# 301_FrameUSB.net
KiCad netlist of a schematic drawn in Altium Designer
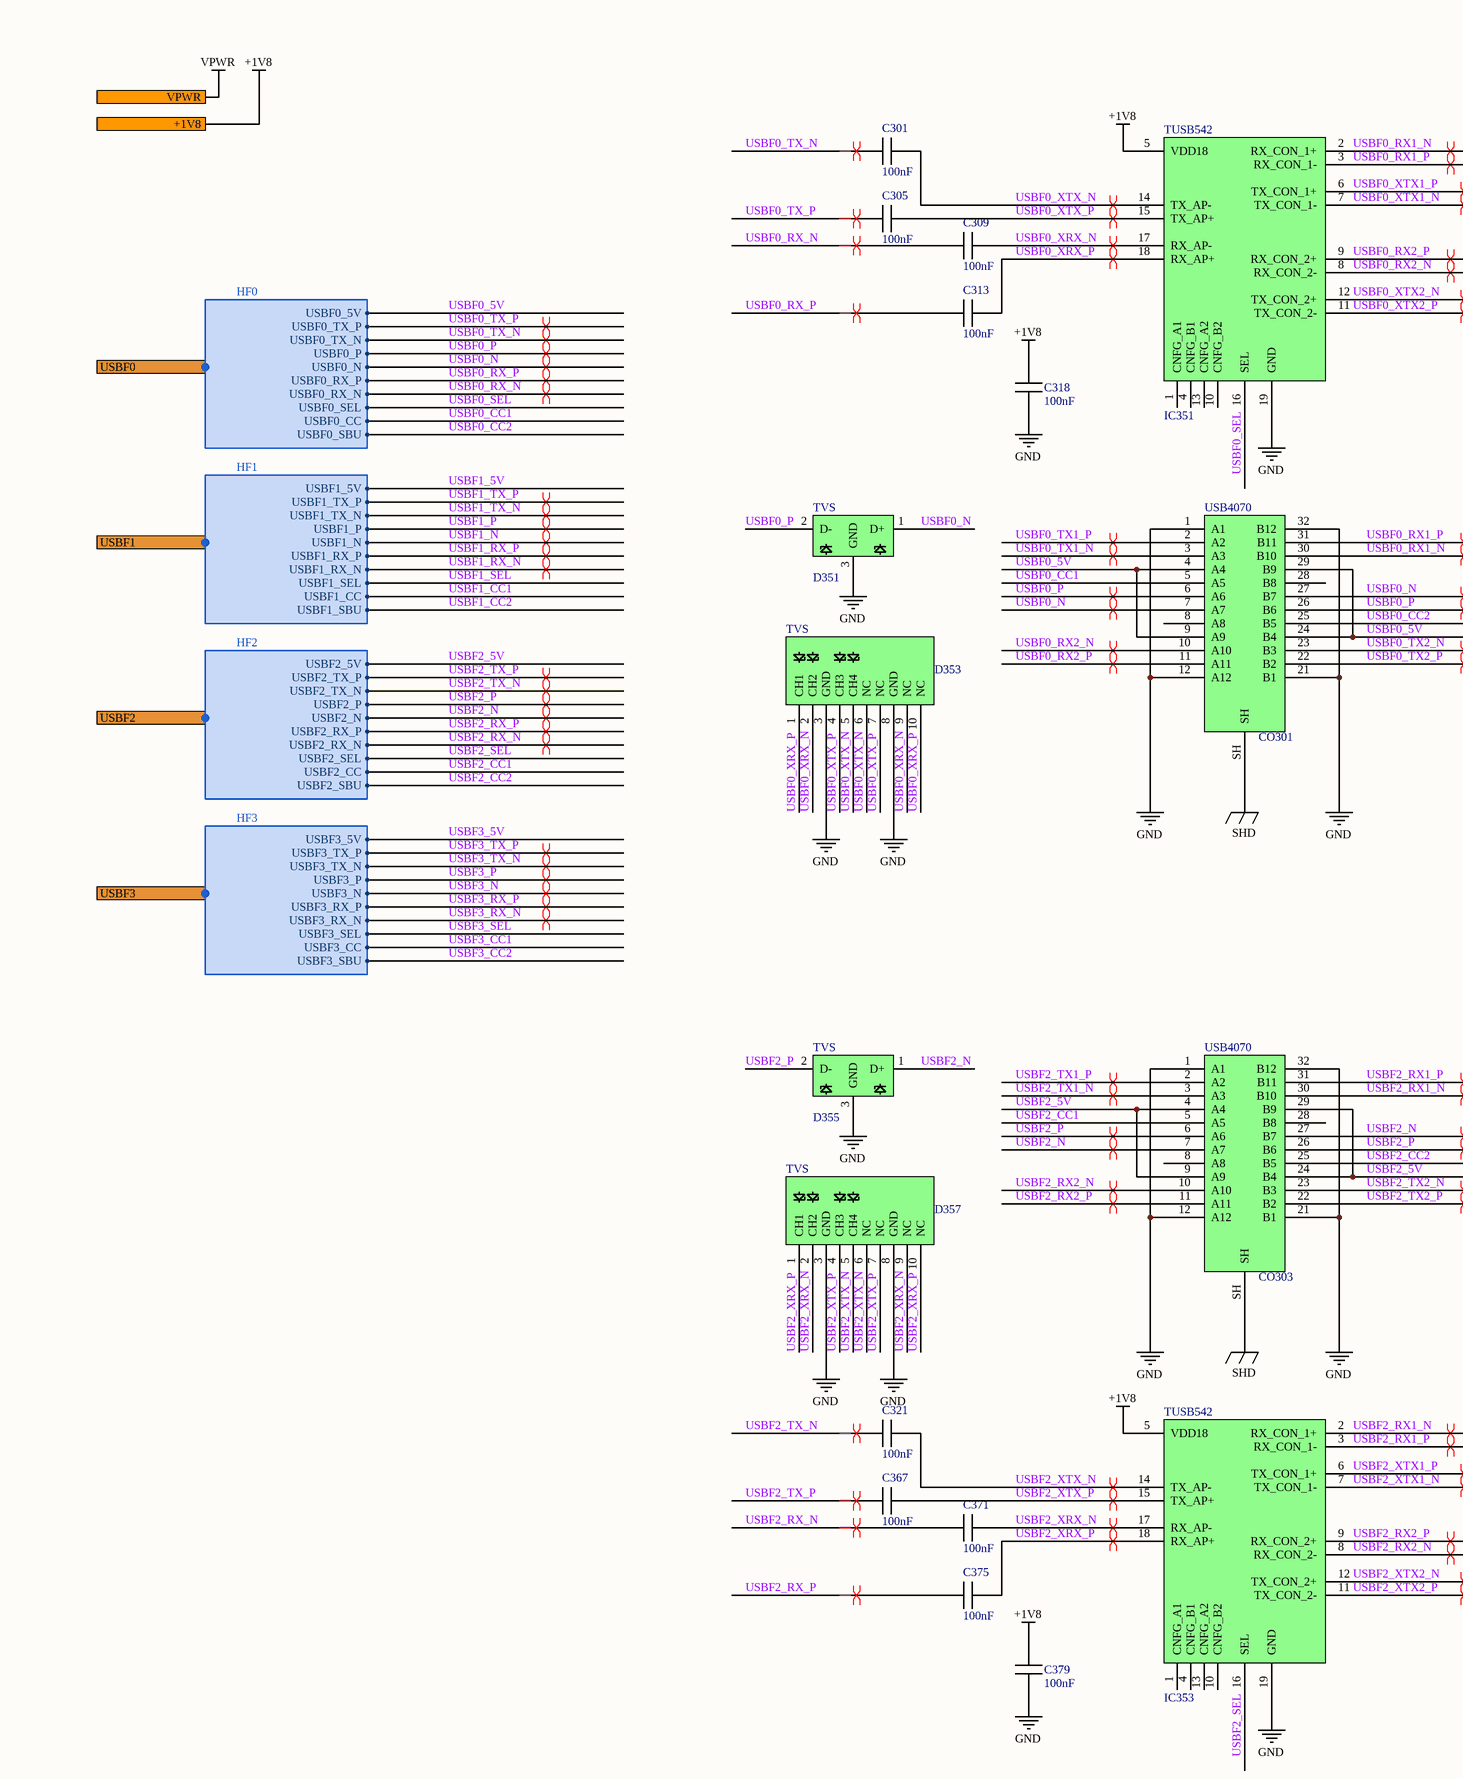
[diagram p0: 301_FrameUSB.SchDoc, top left]
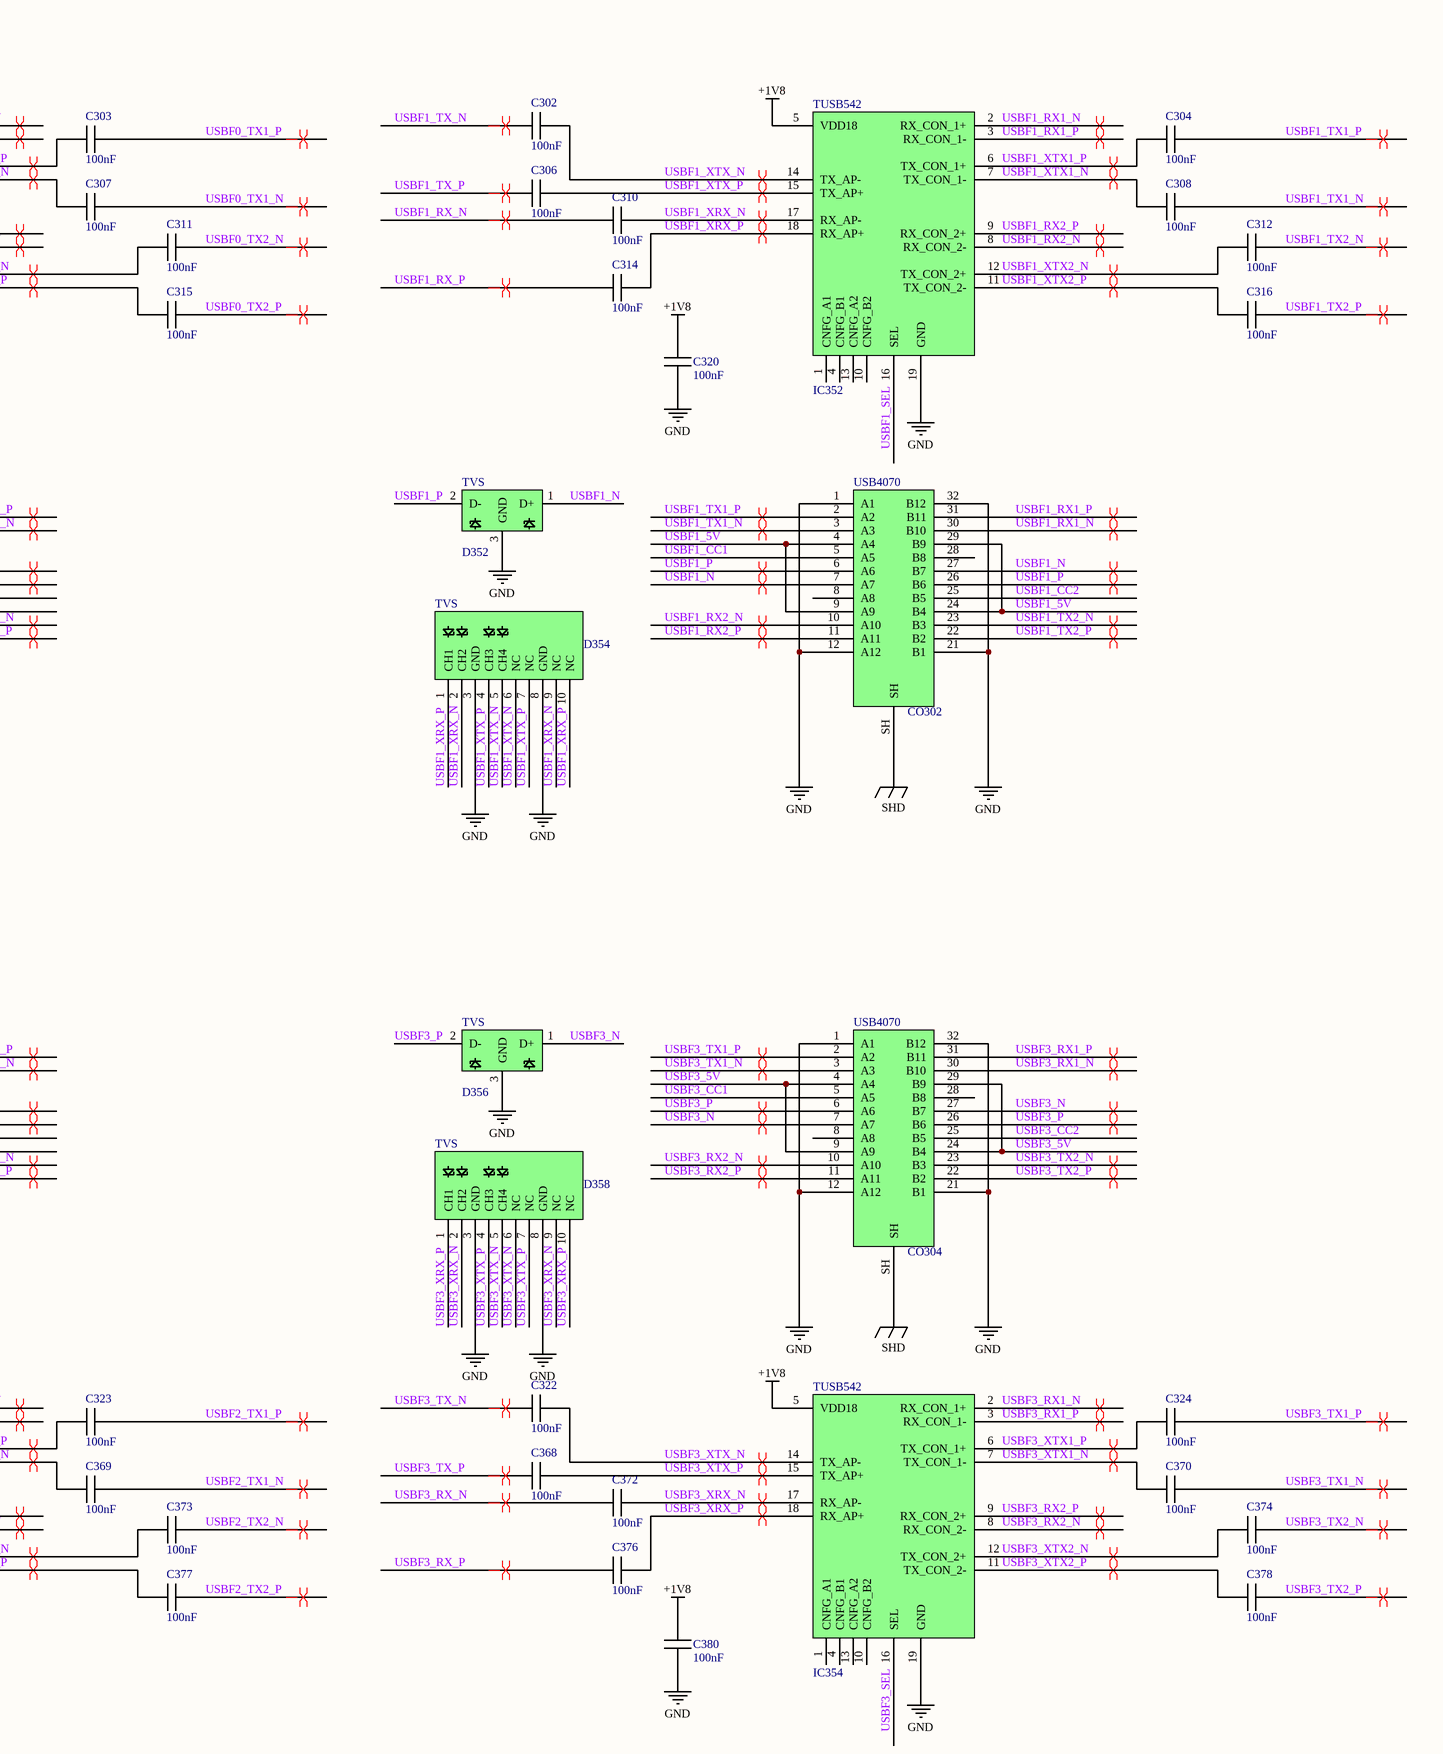
[diagram p1: 301_FrameUSB.SchDoc, top right]
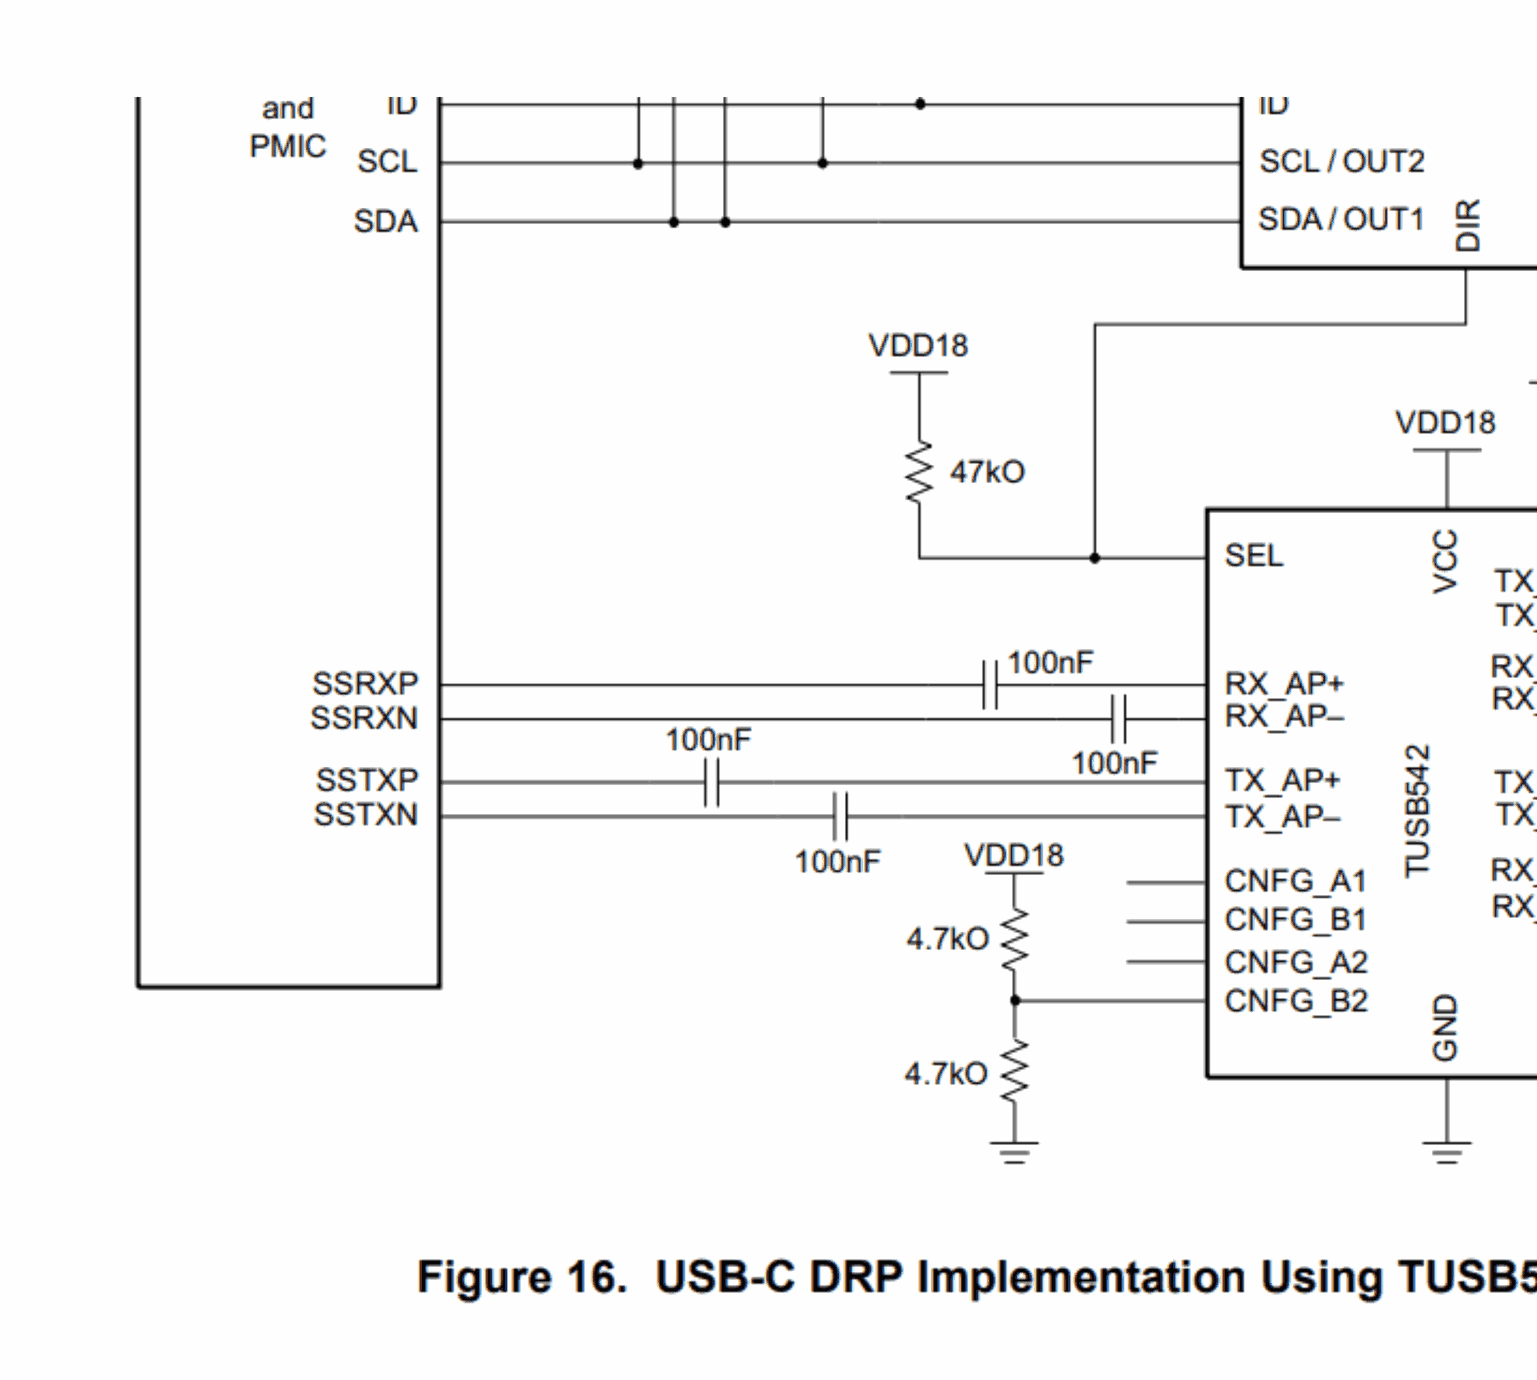
[diagram p2: 301_FrameUSB.SchDoc, bottom left]
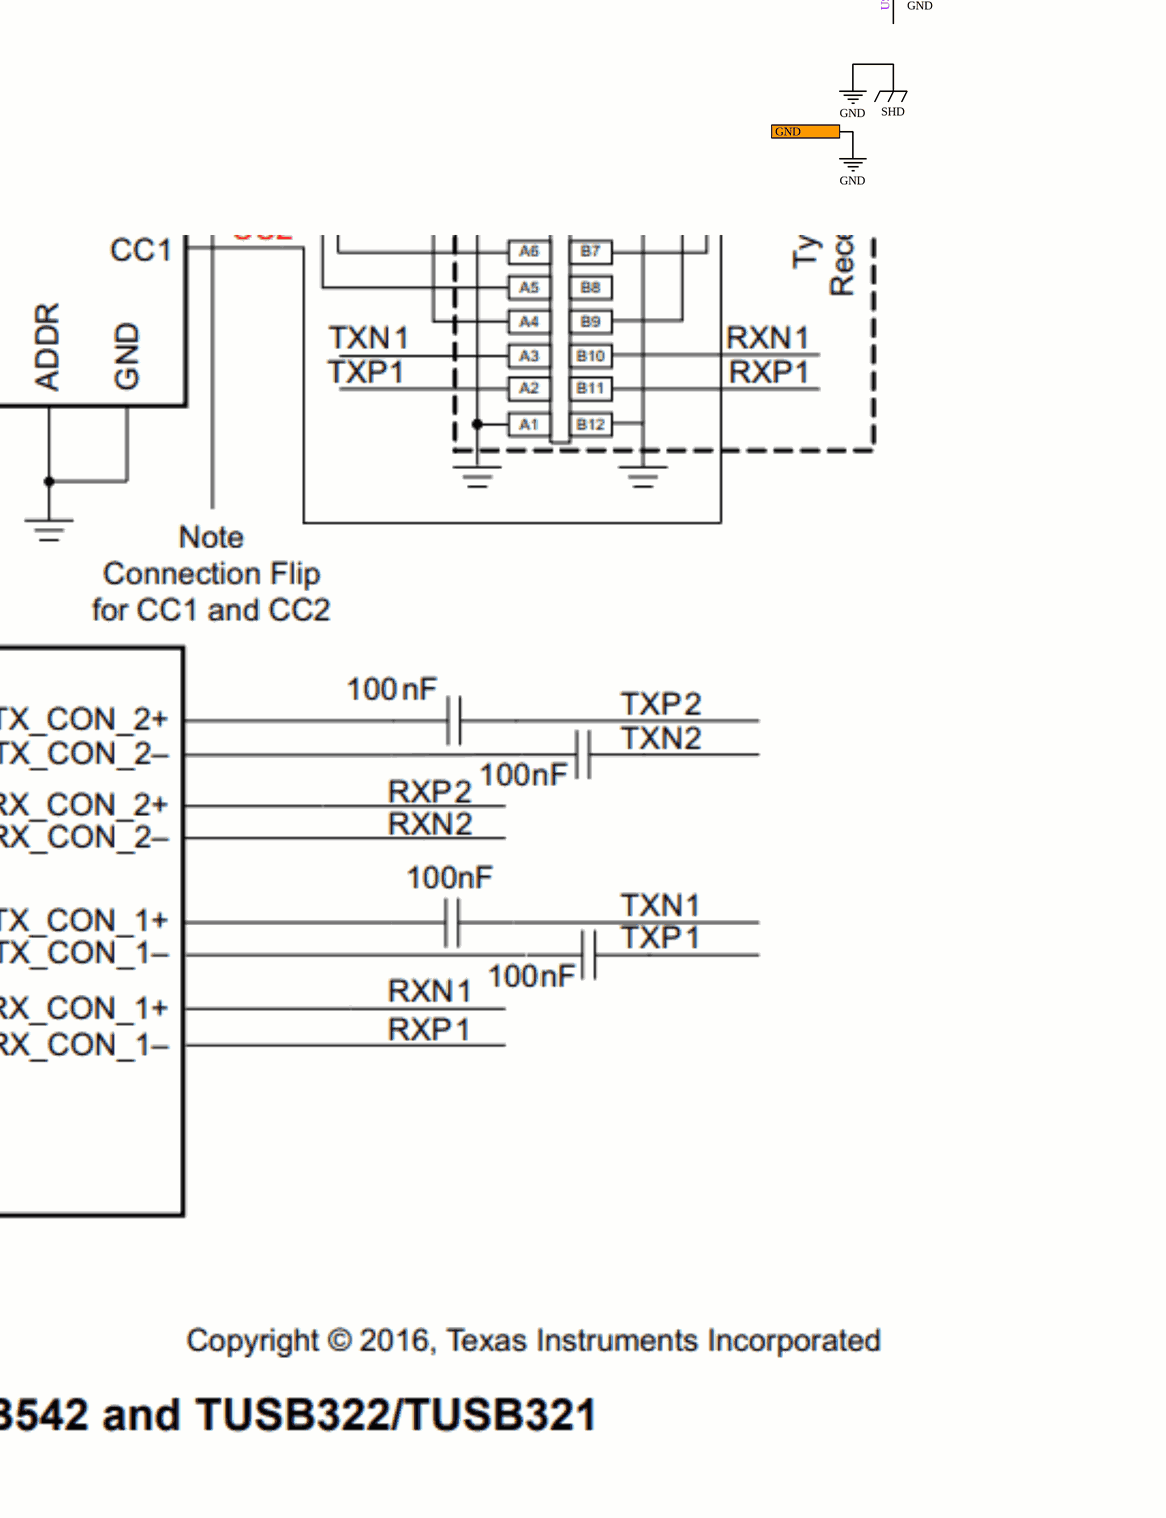
[diagram p3: 301_FrameUSB.SchDoc, bottom right]

(export (version "E")
  (design (tool "Eeschema 10.0.6"))
  (components
    (comp (ref "C301")
      (value "100nF")
      (footprint "C0402")
      (description "100nF 16V 10% X7R")
      (fields
        (field (name "REFVAL") "100nF")
        (field (name "PART NUMBER") "CA0010")
        (field (name "MANFACTPART") "GCM155R71C104KA55D")
      )
      (libsource (lib "GTS_Database") (part "C"))
    )
    (comp (ref "C302")
      (value "100nF")
      (footprint "C0402")
      (description "100nF 16V 10% X7R")
      (fields
        (field (name "REFVAL") "100nF")
        (field (name "PART NUMBER") "CA0010")
        (field (name "MANFACTPART") "GCM155R71C104KA55D")
      )
      (libsource (lib "GTS_Database") (part "C"))
    )
    (comp (ref "C303")
      (value "100nF")
      (footprint "C0402")
      (description "100nF 16V 10% X7R")
      (fields
        (field (name "REFVAL") "100nF")
        (field (name "PART NUMBER") "CA0010")
        (field (name "MANFACTPART") "GCM155R71C104KA55D")
      )
      (libsource (lib "GTS_Database") (part "C"))
    )
    (comp (ref "C304")
      (value "100nF")
      (footprint "C0402")
      (description "100nF 16V 10% X7R")
      (fields
        (field (name "REFVAL") "100nF")
        (field (name "PART NUMBER") "CA0010")
        (field (name "MANFACTPART") "GCM155R71C104KA55D")
      )
      (libsource (lib "GTS_Database") (part "C"))
    )
    (comp (ref "C305")
      (value "100nF")
      (footprint "C0402")
      (description "100nF 16V 10% X7R")
      (fields
        (field (name "REFVAL") "100nF")
        (field (name "PART NUMBER") "CA0010")
        (field (name "MANFACTPART") "GCM155R71C104KA55D")
      )
      (libsource (lib "GTS_Database") (part "C"))
    )
    (comp (ref "C306")
      (value "100nF")
      (footprint "C0402")
      (description "100nF 16V 10% X7R")
      (fields
        (field (name "REFVAL") "100nF")
        (field (name "PART NUMBER") "CA0010")
        (field (name "MANFACTPART") "GCM155R71C104KA55D")
      )
      (libsource (lib "GTS_Database") (part "C"))
    )
    (comp (ref "C307")
      (value "100nF")
      (footprint "C0402")
      (description "100nF 16V 10% X7R")
      (fields
        (field (name "REFVAL") "100nF")
        (field (name "PART NUMBER") "CA0010")
        (field (name "MANFACTPART") "GCM155R71C104KA55D")
      )
      (libsource (lib "GTS_Database") (part "C"))
    )
    (comp (ref "C308")
      (value "100nF")
      (footprint "C0402")
      (description "100nF 16V 10% X7R")
      (fields
        (field (name "REFVAL") "100nF")
        (field (name "PART NUMBER") "CA0010")
        (field (name "MANFACTPART") "GCM155R71C104KA55D")
      )
      (libsource (lib "GTS_Database") (part "C"))
    )
    (comp (ref "C309")
      (value "100nF")
      (footprint "C0402")
      (description "100nF 16V 10% X7R")
      (fields
        (field (name "REFVAL") "100nF")
        (field (name "PART NUMBER") "CA0010")
        (field (name "MANFACTPART") "GCM155R71C104KA55D")
      )
      (libsource (lib "GTS_Database") (part "C"))
    )
    (comp (ref "C310")
      (value "100nF")
      (footprint "C0402")
      (description "100nF 16V 10% X7R")
      (fields
        (field (name "REFVAL") "100nF")
        (field (name "PART NUMBER") "CA0010")
        (field (name "MANFACTPART") "GCM155R71C104KA55D")
      )
      (libsource (lib "GTS_Database") (part "C"))
    )
    (comp (ref "C311")
      (value "100nF")
      (footprint "C0402")
      (description "100nF 16V 10% X7R")
      (fields
        (field (name "REFVAL") "100nF")
        (field (name "PART NUMBER") "CA0010")
        (field (name "MANFACTPART") "GCM155R71C104KA55D")
      )
      (libsource (lib "GTS_Database") (part "C"))
    )
    (comp (ref "C312")
      (value "100nF")
      (footprint "C0402")
      (description "100nF 16V 10% X7R")
      (fields
        (field (name "REFVAL") "100nF")
        (field (name "PART NUMBER") "CA0010")
        (field (name "MANFACTPART") "GCM155R71C104KA55D")
      )
      (libsource (lib "GTS_Database") (part "C"))
    )
    (comp (ref "C313")
      (value "100nF")
      (footprint "C0402")
      (description "100nF 16V 10% X7R")
      (fields
        (field (name "REFVAL") "100nF")
        (field (name "PART NUMBER") "CA0010")
        (field (name "MANFACTPART") "GCM155R71C104KA55D")
      )
      (libsource (lib "GTS_Database") (part "C"))
    )
    (comp (ref "C314")
      (value "100nF")
      (footprint "C0402")
      (description "100nF 16V 10% X7R")
      (fields
        (field (name "REFVAL") "100nF")
        (field (name "PART NUMBER") "CA0010")
        (field (name "MANFACTPART") "GCM155R71C104KA55D")
      )
      (libsource (lib "GTS_Database") (part "C"))
    )
    (comp (ref "C315")
      (value "100nF")
      (footprint "C0402")
      (description "100nF 16V 10% X7R")
      (fields
        (field (name "REFVAL") "100nF")
        (field (name "PART NUMBER") "CA0010")
        (field (name "MANFACTPART") "GCM155R71C104KA55D")
      )
      (libsource (lib "GTS_Database") (part "C"))
    )
    (comp (ref "C316")
      (value "100nF")
      (footprint "C0402")
      (description "100nF 16V 10% X7R")
      (fields
        (field (name "REFVAL") "100nF")
        (field (name "PART NUMBER") "CA0010")
        (field (name "MANFACTPART") "GCM155R71C104KA55D")
      )
      (libsource (lib "GTS_Database") (part "C"))
    )
    (comp (ref "C318")
      (value "100nF")
      (footprint "C0402")
      (description "100nF 16V 10% X7R")
      (fields
        (field (name "REFVAL") "100nF")
        (field (name "PART NUMBER") "CA0010")
        (field (name "MANFACTPART") "GCM155R71C104KA55D")
      )
      (libsource (lib "GTS_Database") (part "C"))
    )
    (comp (ref "C320")
      (value "100nF")
      (footprint "C0402")
      (description "100nF 16V 10% X7R")
      (fields
        (field (name "REFVAL") "100nF")
        (field (name "PART NUMBER") "CA0010")
        (field (name "MANFACTPART") "GCM155R71C104KA55D")
      )
      (libsource (lib "GTS_Database") (part "C"))
    )
    (comp (ref "C321")
      (value "100nF")
      (footprint "C0402")
      (description "100nF 16V 10% X7R")
      (fields
        (field (name "REFVAL") "100nF")
        (field (name "PART NUMBER") "CA0010")
        (field (name "MANFACTPART") "GCM155R71C104KA55D")
      )
      (libsource (lib "GTS_Database") (part "C"))
    )
    (comp (ref "C322")
      (value "100nF")
      (footprint "C0402")
      (description "100nF 16V 10% X7R")
      (fields
        (field (name "REFVAL") "100nF")
        (field (name "PART NUMBER") "CA0010")
        (field (name "MANFACTPART") "GCM155R71C104KA55D")
      )
      (libsource (lib "GTS_Database") (part "C"))
    )
    (comp (ref "C323")
      (value "100nF")
      (footprint "C0402")
      (description "100nF 16V 10% X7R")
      (fields
        (field (name "REFVAL") "100nF")
        (field (name "PART NUMBER") "CA0010")
        (field (name "MANFACTPART") "GCM155R71C104KA55D")
      )
      (libsource (lib "GTS_Database") (part "C"))
    )
    (comp (ref "C324")
      (value "100nF")
      (footprint "C0402")
      (description "100nF 16V 10% X7R")
      (fields
        (field (name "REFVAL") "100nF")
        (field (name "PART NUMBER") "CA0010")
        (field (name "MANFACTPART") "GCM155R71C104KA55D")
      )
      (libsource (lib "GTS_Database") (part "C"))
    )
    (comp (ref "C367")
      (value "100nF")
      (footprint "C0402")
      (description "100nF 16V 10% X7R")
      (fields
        (field (name "REFVAL") "100nF")
        (field (name "PART NUMBER") "CA0010")
        (field (name "MANFACTPART") "GCM155R71C104KA55D")
      )
      (libsource (lib "GTS_Database") (part "C"))
    )
    (comp (ref "C368")
      (value "100nF")
      (footprint "C0402")
      (description "100nF 16V 10% X7R")
      (fields
        (field (name "REFVAL") "100nF")
        (field (name "PART NUMBER") "CA0010")
        (field (name "MANFACTPART") "GCM155R71C104KA55D")
      )
      (libsource (lib "GTS_Database") (part "C"))
    )
    (comp (ref "C369")
      (value "100nF")
      (footprint "C0402")
      (description "100nF 16V 10% X7R")
      (fields
        (field (name "REFVAL") "100nF")
        (field (name "PART NUMBER") "CA0010")
        (field (name "MANFACTPART") "GCM155R71C104KA55D")
      )
      (libsource (lib "GTS_Database") (part "C"))
    )
    (comp (ref "C370")
      (value "100nF")
      (footprint "C0402")
      (description "100nF 16V 10% X7R")
      (fields
        (field (name "REFVAL") "100nF")
        (field (name "PART NUMBER") "CA0010")
        (field (name "MANFACTPART") "GCM155R71C104KA55D")
      )
      (libsource (lib "GTS_Database") (part "C"))
    )
    (comp (ref "C371")
      (value "100nF")
      (footprint "C0402")
      (description "100nF 16V 10% X7R")
      (fields
        (field (name "REFVAL") "100nF")
        (field (name "PART NUMBER") "CA0010")
        (field (name "MANFACTPART") "GCM155R71C104KA55D")
      )
      (libsource (lib "GTS_Database") (part "C"))
    )
    (comp (ref "C372")
      (value "100nF")
      (footprint "C0402")
      (description "100nF 16V 10% X7R")
      (fields
        (field (name "REFVAL") "100nF")
        (field (name "PART NUMBER") "CA0010")
        (field (name "MANFACTPART") "GCM155R71C104KA55D")
      )
      (libsource (lib "GTS_Database") (part "C"))
    )
    (comp (ref "C373")
      (value "100nF")
      (footprint "C0402")
      (description "100nF 16V 10% X7R")
      (fields
        (field (name "REFVAL") "100nF")
        (field (name "PART NUMBER") "CA0010")
        (field (name "MANFACTPART") "GCM155R71C104KA55D")
      )
      (libsource (lib "GTS_Database") (part "C"))
    )
    (comp (ref "C374")
      (value "100nF")
      (footprint "C0402")
      (description "100nF 16V 10% X7R")
      (fields
        (field (name "REFVAL") "100nF")
        (field (name "PART NUMBER") "CA0010")
        (field (name "MANFACTPART") "GCM155R71C104KA55D")
      )
      (libsource (lib "GTS_Database") (part "C"))
    )
    (comp (ref "C375")
      (value "100nF")
      (footprint "C0402")
      (description "100nF 16V 10% X7R")
      (fields
        (field (name "REFVAL") "100nF")
        (field (name "PART NUMBER") "CA0010")
        (field (name "MANFACTPART") "GCM155R71C104KA55D")
      )
      (libsource (lib "GTS_Database") (part "C"))
    )
    (comp (ref "C376")
      (value "100nF")
      (footprint "C0402")
      (description "100nF 16V 10% X7R")
      (fields
        (field (name "REFVAL") "100nF")
        (field (name "PART NUMBER") "CA0010")
        (field (name "MANFACTPART") "GCM155R71C104KA55D")
      )
      (libsource (lib "GTS_Database") (part "C"))
    )
    (comp (ref "C377")
      (value "100nF")
      (footprint "C0402")
      (description "100nF 16V 10% X7R")
      (fields
        (field (name "REFVAL") "100nF")
        (field (name "PART NUMBER") "CA0010")
        (field (name "MANFACTPART") "GCM155R71C104KA55D")
      )
      (libsource (lib "GTS_Database") (part "C"))
    )
    (comp (ref "C378")
      (value "100nF")
      (footprint "C0402")
      (description "100nF 16V 10% X7R")
      (fields
        (field (name "REFVAL") "100nF")
        (field (name "PART NUMBER") "CA0010")
        (field (name "MANFACTPART") "GCM155R71C104KA55D")
      )
      (libsource (lib "GTS_Database") (part "C"))
    )
    (comp (ref "C379")
      (value "100nF")
      (footprint "C0402")
      (description "100nF 16V 10% X7R")
      (fields
        (field (name "REFVAL") "100nF")
        (field (name "PART NUMBER") "CA0010")
        (field (name "MANFACTPART") "GCM155R71C104KA55D")
      )
      (libsource (lib "GTS_Database") (part "C"))
    )
    (comp (ref "C380")
      (value "100nF")
      (footprint "C0402")
      (description "100nF 16V 10% X7R")
      (fields
        (field (name "REFVAL") "100nF")
        (field (name "PART NUMBER") "CA0010")
        (field (name "MANFACTPART") "GCM155R71C104KA55D")
      )
      (libsource (lib "GTS_Database") (part "C"))
    )
    (comp (ref "CO301")
      (value "USB4070")
      (footprint "USB4070-30-C")
      (description "USB C connector Receptacle Vertical")
      (fields
        (field (name "REFVAL") "USB4070")
        (field (name "PART NUMBER") "CO0021")
        (field (name "MANFACTPART") "USB4070-30-C")
      )
      (libsource (lib "GTS_Database") (part "USB-CC"))
    )
    (comp (ref "CO302")
      (value "USB4070")
      (footprint "USB4070-30-C")
      (description "USB C connector Receptacle Vertical")
      (fields
        (field (name "REFVAL") "USB4070")
        (field (name "PART NUMBER") "CO0021")
        (field (name "MANFACTPART") "USB4070-30-C")
      )
      (libsource (lib "GTS_Database") (part "USB-CC"))
    )
    (comp (ref "CO303")
      (value "USB4070")
      (footprint "USB4070-30-C")
      (description "USB C connector Receptacle Vertical")
      (fields
        (field (name "REFVAL") "USB4070")
        (field (name "PART NUMBER") "CO0021")
        (field (name "MANFACTPART") "USB4070-30-C")
      )
      (libsource (lib "GTS_Database") (part "USB-CC"))
    )
    (comp (ref "CO304")
      (value "USB4070")
      (footprint "USB4070-30-C")
      (description "USB C connector Receptacle Vertical")
      (fields
        (field (name "REFVAL") "USB4070")
        (field (name "PART NUMBER") "CO0021")
        (field (name "MANFACTPART") "USB4070-30-C")
      )
      (libsource (lib "GTS_Database") (part "USB-CC"))
    )
    (comp (ref "D351")
      (value "TVS")
      (footprint "SOT-3")
      (description "USB 2 TVS Diode")
      (fields
        (field (name "REFVAL") "TVS")
        (field (name "PART NUMBER") "DI0002")
        (field (name "MANFACTPART") "TPD2EUSB30DRTR")
      )
      (libsource (lib "GTS_Database") (part "USB2TVS"))
    )
    (comp (ref "D352")
      (value "TVS")
      (footprint "SOT-3")
      (description "USB 2 TVS Diode")
      (fields
        (field (name "REFVAL") "TVS")
        (field (name "PART NUMBER") "DI0002")
        (field (name "MANFACTPART") "TPD2EUSB30DRTR")
      )
      (libsource (lib "GTS_Database") (part "USB2TVS"))
    )
    (comp (ref "D353")
      (value "TVS")
      (footprint "SOT-1176-1")
      (description "USB 3 TVS Diode")
      (fields
        (field (name "REFVAL") "TVS")
        (field (name "PART NUMBER") "DI0007")
        (field (name "MANFACTPART") "PUSB3FA2Z")
      )
      (libsource (lib "GTS_Database") (part "USB3TVS"))
    )
    (comp (ref "D354")
      (value "TVS")
      (footprint "SOT-1176-1")
      (description "USB 3 TVS Diode")
      (fields
        (field (name "REFVAL") "TVS")
        (field (name "PART NUMBER") "DI0007")
        (field (name "MANFACTPART") "PUSB3FA2Z")
      )
      (libsource (lib "GTS_Database") (part "USB3TVS"))
    )
    (comp (ref "D355")
      (value "TVS")
      (footprint "SOT-3")
      (description "USB 2 TVS Diode")
      (fields
        (field (name "REFVAL") "TVS")
        (field (name "PART NUMBER") "DI0002")
        (field (name "MANFACTPART") "TPD2EUSB30DRTR")
      )
      (libsource (lib "GTS_Database") (part "USB2TVS"))
    )
    (comp (ref "D356")
      (value "TVS")
      (footprint "SOT-3")
      (description "USB 2 TVS Diode")
      (fields
        (field (name "REFVAL") "TVS")
        (field (name "PART NUMBER") "DI0002")
        (field (name "MANFACTPART") "TPD2EUSB30DRTR")
      )
      (libsource (lib "GTS_Database") (part "USB2TVS"))
    )
    (comp (ref "D357")
      (value "TVS")
      (footprint "SOT-1176-1")
      (description "USB 3 TVS Diode")
      (fields
        (field (name "REFVAL") "TVS")
        (field (name "PART NUMBER") "DI0007")
        (field (name "MANFACTPART") "PUSB3FA2Z")
      )
      (libsource (lib "GTS_Database") (part "USB3TVS"))
    )
    (comp (ref "D358")
      (value "TVS")
      (footprint "SOT-1176-1")
      (description "USB 3 TVS Diode")
      (fields
        (field (name "REFVAL") "TVS")
        (field (name "PART NUMBER") "DI0007")
        (field (name "MANFACTPART") "PUSB3FA2Z")
      )
      (libsource (lib "GTS_Database") (part "USB3TVS"))
    )
    (comp (ref "IC351")
      (value "TUSB542")
      (footprint "X2QFN-18G_2.4X2")
      (description "TUSB542 USB Type-C 5 Gbps Redriver 2:1 MUX")
      (fields (field (name "REFVAL") "TUSB542") (field (name "PART NUMBER") "IC0039"))
      (libsource (lib "GTS_Database") (part "TUSB542"))
    )
    (comp (ref "IC352")
      (value "TUSB542")
      (footprint "X2QFN-18G_2.4X2")
      (description "TUSB542 USB Type-C 5 Gbps Redriver 2:1 MUX")
      (fields (field (name "REFVAL") "TUSB542") (field (name "PART NUMBER") "IC0039"))
      (libsource (lib "GTS_Database") (part "TUSB542"))
    )
    (comp (ref "IC353")
      (value "TUSB542")
      (footprint "X2QFN-18G_2.4X2")
      (description "TUSB542 USB Type-C 5 Gbps Redriver 2:1 MUX")
      (fields (field (name "REFVAL") "TUSB542") (field (name "PART NUMBER") "IC0039"))
      (libsource (lib "GTS_Database") (part "TUSB542"))
    )
    (comp (ref "IC354")
      (value "TUSB542")
      (footprint "X2QFN-18G_2.4X2")
      (description "TUSB542 USB Type-C 5 Gbps Redriver 2:1 MUX")
      (fields (field (name "REFVAL") "TUSB542") (field (name "PART NUMBER") "IC0039"))
      (libsource (lib "GTS_Database") (part "TUSB542"))
    )
  )
  (nets
    (net (code "5") (name "+1V8") (class "Default")
      (node (ref "C318") (pin "1") (pinfunction "1_1") (pintype "passive"))
      (node (ref "C320") (pin "1") (pinfunction "1_1") (pintype "passive"))
      (node (ref "C379") (pin "1") (pinfunction "1_1") (pintype "passive"))
      (node (ref "C380") (pin "1") (pinfunction "1_1") (pintype "passive"))
      (node (ref "IC351") (pin "5") (pinfunction "VDD18_5") (pintype "passive"))
      (node (ref "IC352") (pin "5") (pinfunction "VDD18_5") (pintype "passive"))
      (node (ref "IC353") (pin "5") (pinfunction "VDD18_5") (pintype "passive"))
      (node (ref "IC354") (pin "5") (pinfunction "VDD18_5") (pintype "passive"))
    )
    (net (code "6") (name "/USBF0_5V") (class "Default")
      (node (ref "CO301") (pin "24") (pinfunction "B4_24") (pintype "passive"))
      (node (ref "CO301") (pin "29") (pinfunction "B9_29") (pintype "passive"))
      (node (ref "CO301") (pin "4") (pinfunction "A4_4") (pintype "passive"))
      (node (ref "CO301") (pin "9") (pinfunction "A9_9") (pintype "passive"))
    )
    (net (code "7") (name "/USBF0_CC1") (class "Default")
      (node (ref "CO301") (pin "5") (pinfunction "A5_5") (pintype "passive"))
    )
    (net (code "8") (name "/USBF0_CC2") (class "Default")
      (node (ref "CO301") (pin "25") (pinfunction "B5_25") (pintype "passive"))
    )
    (net (code "9") (name "/USBF0_N") (class "Default")
      (node (ref "CO301") (pin "27") (pinfunction "B7_27") (pintype "passive"))
      (node (ref "CO301") (pin "7") (pinfunction "A7_7") (pintype "passive"))
      (node (ref "D351") (pin "1") (pinfunction "D+_1") (pintype "passive"))
    )
    (net (code "10") (name "/USBF0_P") (class "Default")
      (node (ref "CO301") (pin "26") (pinfunction "B6_26") (pintype "passive"))
      (node (ref "CO301") (pin "6") (pinfunction "A6_6") (pintype "passive"))
      (node (ref "D351") (pin "2") (pinfunction "D-_2") (pintype "passive"))
    )
    (net (code "11") (name "/USBF0_RX1_N") (class "Default")
      (node (ref "CO301") (pin "30") (pinfunction "B10_30") (pintype "passive"))
      (node (ref "IC351") (pin "2") (pinfunction "RX_CON_1+_2") (pintype "passive"))
    )
    (net (code "12") (name "/USBF0_RX1_P") (class "Default")
      (node (ref "CO301") (pin "31") (pinfunction "B11_31") (pintype "passive"))
      (node (ref "IC351") (pin "3") (pinfunction "RX_CON_1-_3") (pintype "passive"))
    )
    (net (code "13") (name "/USBF0_RX2_N") (class "Default")
      (node (ref "CO301") (pin "10") (pinfunction "A10_10") (pintype "passive"))
      (node (ref "IC351") (pin "8") (pinfunction "RX_CON_2-_8") (pintype "passive"))
    )
    (net (code "14") (name "/USBF0_RX2_P") (class "Default")
      (node (ref "CO301") (pin "11") (pinfunction "A11_11") (pintype "passive"))
      (node (ref "IC351") (pin "9") (pinfunction "RX_CON_2+_9") (pintype "passive"))
    )
    (net (code "15") (name "/USBF0_RX_N") (class "Default")
      (node (ref "C309") (pin "1") (pinfunction "1_1") (pintype "passive"))
    )
    (net (code "16") (name "/USBF0_RX_P") (class "Default")
      (node (ref "C313") (pin "1") (pinfunction "1_1") (pintype "passive"))
    )
    (net (code "17") (name "/USBF0_SEL") (class "Default")
      (node (ref "IC351") (pin "16") (pinfunction "SEL_16") (pintype "passive"))
    )
    (net (code "18") (name "/USBF0_TX1_N") (class "Default")
      (node (ref "C307") (pin "2") (pinfunction "2_2") (pintype "passive"))
      (node (ref "CO301") (pin "3") (pinfunction "A3_3") (pintype "passive"))
    )
    (net (code "19") (name "/USBF0_TX1_P") (class "Default")
      (node (ref "C303") (pin "2") (pinfunction "2_2") (pintype "passive"))
      (node (ref "CO301") (pin "2") (pinfunction "A2_2") (pintype "passive"))
    )
    (net (code "20") (name "/USBF0_TX2_N") (class "Default")
      (node (ref "C311") (pin "2") (pinfunction "2_2") (pintype "passive"))
      (node (ref "CO301") (pin "23") (pinfunction "B3_23") (pintype "passive"))
    )
    (net (code "21") (name "/USBF0_TX2_P") (class "Default")
      (node (ref "C315") (pin "2") (pinfunction "2_2") (pintype "passive"))
      (node (ref "CO301") (pin "22") (pinfunction "B2_22") (pintype "passive"))
    )
    (net (code "22") (name "/USBF0_TX_N") (class "Default")
      (node (ref "C301") (pin "1") (pinfunction "1_1") (pintype "passive"))
    )
    (net (code "23") (name "/USBF0_TX_P") (class "Default")
      (node (ref "C305") (pin "1") (pinfunction "1_1") (pintype "passive"))
    )
    (net (code "24") (name "/USBF0_XRX_N") (class "Default")
      (node (ref "C309") (pin "2") (pinfunction "2_2") (pintype "passive"))
      (node (ref "D353") (pin "2") (pinfunction "CH2_2") (pintype "passive"))
      (node (ref "D353") (pin "9") (pinfunction "NC_9") (pintype "passive"))
      (node (ref "IC351") (pin "17") (pinfunction "RX_AP-_17") (pintype "passive"))
    )
    (net (code "25") (name "/USBF0_XRX_P") (class "Default")
      (node (ref "C313") (pin "2") (pinfunction "2_2") (pintype "passive"))
      (node (ref "D353") (pin "1") (pinfunction "CH1_1") (pintype "passive"))
      (node (ref "D353") (pin "10") (pinfunction "NC_10") (pintype "passive"))
      (node (ref "IC351") (pin "18") (pinfunction "RX_AP+_18") (pintype "passive"))
    )
    (net (code "26") (name "/USBF0_XTX1_N") (class "Default")
      (node (ref "C307") (pin "1") (pinfunction "1_1") (pintype "passive"))
      (node (ref "IC351") (pin "7") (pinfunction "TX_CON_1-_7") (pintype "passive"))
    )
    (net (code "27") (name "/USBF0_XTX1_P") (class "Default")
      (node (ref "C303") (pin "1") (pinfunction "1_1") (pintype "passive"))
      (node (ref "IC351") (pin "6") (pinfunction "TX_CON_1+_6") (pintype "passive"))
    )
    (net (code "28") (name "/USBF0_XTX2_N") (class "Default")
      (node (ref "C311") (pin "1") (pinfunction "1_1") (pintype "passive"))
      (node (ref "IC351") (pin "12") (pinfunction "TX_CON_2+_12") (pintype "passive"))
    )
    (net (code "29") (name "/USBF0_XTX2_P") (class "Default")
      (node (ref "C315") (pin "1") (pinfunction "1_1") (pintype "passive"))
      (node (ref "IC351") (pin "11") (pinfunction "TX_CON_2-_11") (pintype "passive"))
    )
    (net (code "30") (name "/USBF0_XTX_N") (class "Default")
      (node (ref "C301") (pin "2") (pinfunction "2_2") (pintype "passive"))
      (node (ref "D353") (pin "5") (pinfunction "CH4_5") (pintype "passive"))
      (node (ref "D353") (pin "6") (pinfunction "NC_6") (pintype "passive"))
      (node (ref "IC351") (pin "14") (pinfunction "TX_AP-_14") (pintype "passive"))
    )
    (net (code "31") (name "/USBF0_XTX_P") (class "Default")
      (node (ref "C305") (pin "2") (pinfunction "2_2") (pintype "passive"))
      (node (ref "D353") (pin "4") (pinfunction "CH3_4") (pintype "passive"))
      (node (ref "D353") (pin "7") (pinfunction "NC_7") (pintype "passive"))
      (node (ref "IC351") (pin "15") (pinfunction "TX_AP+_15") (pintype "passive"))
    )
    (net (code "32") (name "/USBF1_5V") (class "Default")
      (node (ref "CO302") (pin "24") (pinfunction "B4_24") (pintype "passive"))
      (node (ref "CO302") (pin "29") (pinfunction "B9_29") (pintype "passive"))
      (node (ref "CO302") (pin "4") (pinfunction "A4_4") (pintype "passive"))
      (node (ref "CO302") (pin "9") (pinfunction "A9_9") (pintype "passive"))
    )
    (net (code "33") (name "/USBF1_CC1") (class "Default")
      (node (ref "CO302") (pin "5") (pinfunction "A5_5") (pintype "passive"))
    )
    (net (code "34") (name "/USBF1_CC2") (class "Default")
      (node (ref "CO302") (pin "25") (pinfunction "B5_25") (pintype "passive"))
    )
    (net (code "35") (name "/USBF1_N") (class "Default")
      (node (ref "CO302") (pin "27") (pinfunction "B7_27") (pintype "passive"))
      (node (ref "CO302") (pin "7") (pinfunction "A7_7") (pintype "passive"))
      (node (ref "D352") (pin "1") (pinfunction "D+_1") (pintype "passive"))
    )
    (net (code "36") (name "/USBF1_P") (class "Default")
      (node (ref "CO302") (pin "26") (pinfunction "B6_26") (pintype "passive"))
      (node (ref "CO302") (pin "6") (pinfunction "A6_6") (pintype "passive"))
      (node (ref "D352") (pin "2") (pinfunction "D-_2") (pintype "passive"))
    )
    (net (code "37") (name "/USBF1_RX1_N") (class "Default")
      (node (ref "CO302") (pin "30") (pinfunction "B10_30") (pintype "passive"))
      (node (ref "IC352") (pin "2") (pinfunction "RX_CON_1+_2") (pintype "passive"))
    )
    (net (code "38") (name "/USBF1_RX1_P") (class "Default")
      (node (ref "CO302") (pin "31") (pinfunction "B11_31") (pintype "passive"))
      (node (ref "IC352") (pin "3") (pinfunction "RX_CON_1-_3") (pintype "passive"))
    )
    (net (code "39") (name "/USBF1_RX2_N") (class "Default")
      (node (ref "CO302") (pin "10") (pinfunction "A10_10") (pintype "passive"))
      (node (ref "IC352") (pin "8") (pinfunction "RX_CON_2-_8") (pintype "passive"))
    )
    (net (code "40") (name "/USBF1_RX2_P") (class "Default")
      (node (ref "CO302") (pin "11") (pinfunction "A11_11") (pintype "passive"))
      (node (ref "IC352") (pin "9") (pinfunction "RX_CON_2+_9") (pintype "passive"))
    )
    (net (code "41") (name "/USBF1_RX_N") (class "Default")
      (node (ref "C310") (pin "1") (pinfunction "1_1") (pintype "passive"))
    )
    (net (code "42") (name "/USBF1_RX_P") (class "Default")
      (node (ref "C314") (pin "1") (pinfunction "1_1") (pintype "passive"))
    )
    (net (code "43") (name "/USBF1_SEL") (class "Default")
      (node (ref "IC352") (pin "16") (pinfunction "SEL_16") (pintype "passive"))
    )
    (net (code "44") (name "/USBF1_TX1_N") (class "Default")
      (node (ref "C308") (pin "2") (pinfunction "2_2") (pintype "passive"))
      (node (ref "CO302") (pin "3") (pinfunction "A3_3") (pintype "passive"))
    )
    (net (code "45") (name "/USBF1_TX1_P") (class "Default")
      (node (ref "C304") (pin "2") (pinfunction "2_2") (pintype "passive"))
      (node (ref "CO302") (pin "2") (pinfunction "A2_2") (pintype "passive"))
    )
    (net (code "46") (name "/USBF1_TX2_N") (class "Default")
      (node (ref "C312") (pin "2") (pinfunction "2_2") (pintype "passive"))
      (node (ref "CO302") (pin "23") (pinfunction "B3_23") (pintype "passive"))
    )
    (net (code "47") (name "/USBF1_TX2_P") (class "Default")
      (node (ref "C316") (pin "2") (pinfunction "2_2") (pintype "passive"))
      (node (ref "CO302") (pin "22") (pinfunction "B2_22") (pintype "passive"))
    )
    (net (code "48") (name "/USBF1_TX_N") (class "Default")
      (node (ref "C302") (pin "1") (pinfunction "1_1") (pintype "passive"))
    )
    (net (code "49") (name "/USBF1_TX_P") (class "Default")
      (node (ref "C306") (pin "1") (pinfunction "1_1") (pintype "passive"))
    )
    (net (code "50") (name "/USBF1_XRX_N") (class "Default")
      (node (ref "C310") (pin "2") (pinfunction "2_2") (pintype "passive"))
      (node (ref "D354") (pin "2") (pinfunction "CH2_2") (pintype "passive"))
      (node (ref "D354") (pin "9") (pinfunction "NC_9") (pintype "passive"))
      (node (ref "IC352") (pin "17") (pinfunction "RX_AP-_17") (pintype "passive"))
    )
    (net (code "51") (name "/USBF1_XRX_P") (class "Default")
      (node (ref "C314") (pin "2") (pinfunction "2_2") (pintype "passive"))
      (node (ref "D354") (pin "1") (pinfunction "CH1_1") (pintype "passive"))
      (node (ref "D354") (pin "10") (pinfunction "NC_10") (pintype "passive"))
      (node (ref "IC352") (pin "18") (pinfunction "RX_AP+_18") (pintype "passive"))
    )
    (net (code "52") (name "/USBF1_XTX1_N") (class "Default")
      (node (ref "C308") (pin "1") (pinfunction "1_1") (pintype "passive"))
      (node (ref "IC352") (pin "7") (pinfunction "TX_CON_1-_7") (pintype "passive"))
    )
    (net (code "53") (name "/USBF1_XTX1_P") (class "Default")
      (node (ref "C304") (pin "1") (pinfunction "1_1") (pintype "passive"))
      (node (ref "IC352") (pin "6") (pinfunction "TX_CON_1+_6") (pintype "passive"))
    )
    (net (code "54") (name "/USBF1_XTX2_N") (class "Default")
      (node (ref "C312") (pin "1") (pinfunction "1_1") (pintype "passive"))
      (node (ref "IC352") (pin "12") (pinfunction "TX_CON_2+_12") (pintype "passive"))
    )
    (net (code "55") (name "/USBF1_XTX2_P") (class "Default")
      (node (ref "C316") (pin "1") (pinfunction "1_1") (pintype "passive"))
      (node (ref "IC352") (pin "11") (pinfunction "TX_CON_2-_11") (pintype "passive"))
    )
    (net (code "56") (name "/USBF1_XTX_N") (class "Default")
      (node (ref "C302") (pin "2") (pinfunction "2_2") (pintype "passive"))
      (node (ref "D354") (pin "5") (pinfunction "CH4_5") (pintype "passive"))
      (node (ref "D354") (pin "6") (pinfunction "NC_6") (pintype "passive"))
      (node (ref "IC352") (pin "14") (pinfunction "TX_AP-_14") (pintype "passive"))
    )
    (net (code "57") (name "/USBF1_XTX_P") (class "Default")
      (node (ref "C306") (pin "2") (pinfunction "2_2") (pintype "passive"))
      (node (ref "D354") (pin "4") (pinfunction "CH3_4") (pintype "passive"))
      (node (ref "D354") (pin "7") (pinfunction "NC_7") (pintype "passive"))
      (node (ref "IC352") (pin "15") (pinfunction "TX_AP+_15") (pintype "passive"))
    )
    (net (code "58") (name "/USBF2_5V") (class "Default")
      (node (ref "CO303") (pin "24") (pinfunction "B4_24") (pintype "passive"))
      (node (ref "CO303") (pin "29") (pinfunction "B9_29") (pintype "passive"))
      (node (ref "CO303") (pin "4") (pinfunction "A4_4") (pintype "passive"))
      (node (ref "CO303") (pin "9") (pinfunction "A9_9") (pintype "passive"))
    )
    (net (code "59") (name "/USBF2_CC1") (class "Default")
      (node (ref "CO303") (pin "5") (pinfunction "A5_5") (pintype "passive"))
    )
    (net (code "60") (name "/USBF2_CC2") (class "Default")
      (node (ref "CO303") (pin "25") (pinfunction "B5_25") (pintype "passive"))
    )
    (net (code "61") (name "/USBF2_N") (class "Default")
      (node (ref "CO303") (pin "27") (pinfunction "B7_27") (pintype "passive"))
      (node (ref "CO303") (pin "7") (pinfunction "A7_7") (pintype "passive"))
      (node (ref "D355") (pin "1") (pinfunction "D+_1") (pintype "passive"))
    )
    (net (code "62") (name "/USBF2_P") (class "Default")
      (node (ref "CO303") (pin "26") (pinfunction "B6_26") (pintype "passive"))
      (node (ref "CO303") (pin "6") (pinfunction "A6_6") (pintype "passive"))
      (node (ref "D355") (pin "2") (pinfunction "D-_2") (pintype "passive"))
    )
    (net (code "63") (name "/USBF2_RX1_N") (class "Default")
      (node (ref "CO303") (pin "30") (pinfunction "B10_30") (pintype "passive"))
      (node (ref "IC353") (pin "2") (pinfunction "RX_CON_1+_2") (pintype "passive"))
    )
    (net (code "64") (name "/USBF2_RX1_P") (class "Default")
      (node (ref "CO303") (pin "31") (pinfunction "B11_31") (pintype "passive"))
      (node (ref "IC353") (pin "3") (pinfunction "RX_CON_1-_3") (pintype "passive"))
    )
    (net (code "65") (name "/USBF2_RX2_N") (class "Default")
      (node (ref "CO303") (pin "10") (pinfunction "A10_10") (pintype "passive"))
      (node (ref "IC353") (pin "8") (pinfunction "RX_CON_2-_8") (pintype "passive"))
    )
    (net (code "66") (name "/USBF2_RX2_P") (class "Default")
      (node (ref "CO303") (pin "11") (pinfunction "A11_11") (pintype "passive"))
      (node (ref "IC353") (pin "9") (pinfunction "RX_CON_2+_9") (pintype "passive"))
    )
    (net (code "67") (name "/USBF2_RX_N") (class "Default")
      (node (ref "C371") (pin "1") (pinfunction "1_1") (pintype "passive"))
    )
    (net (code "68") (name "/USBF2_RX_P") (class "Default")
      (node (ref "C375") (pin "1") (pinfunction "1_1") (pintype "passive"))
    )
    (net (code "69") (name "/USBF2_SEL") (class "Default")
      (node (ref "IC353") (pin "16") (pinfunction "SEL_16") (pintype "passive"))
    )
    (net (code "70") (name "/USBF2_TX1_N") (class "Default")
      (node (ref "C369") (pin "2") (pinfunction "2_2") (pintype "passive"))
      (node (ref "CO303") (pin "3") (pinfunction "A3_3") (pintype "passive"))
    )
    (net (code "71") (name "/USBF2_TX1_P") (class "Default")
      (node (ref "C323") (pin "2") (pinfunction "2_2") (pintype "passive"))
      (node (ref "CO303") (pin "2") (pinfunction "A2_2") (pintype "passive"))
    )
    (net (code "72") (name "/USBF2_TX2_N") (class "Default")
      (node (ref "C373") (pin "2") (pinfunction "2_2") (pintype "passive"))
      (node (ref "CO303") (pin "23") (pinfunction "B3_23") (pintype "passive"))
    )
    (net (code "73") (name "/USBF2_TX2_P") (class "Default")
      (node (ref "C377") (pin "2") (pinfunction "2_2") (pintype "passive"))
      (node (ref "CO303") (pin "22") (pinfunction "B2_22") (pintype "passive"))
    )
    (net (code "74") (name "/USBF2_TX_N") (class "Default")
      (node (ref "C321") (pin "1") (pinfunction "1_1") (pintype "passive"))
    )
    (net (code "75") (name "/USBF2_TX_P") (class "Default")
      (node (ref "C367") (pin "1") (pinfunction "1_1") (pintype "passive"))
    )
    (net (code "76") (name "/USBF2_XRX_N") (class "Default")
      (node (ref "C371") (pin "2") (pinfunction "2_2") (pintype "passive"))
      (node (ref "D357") (pin "2") (pinfunction "CH2_2") (pintype "passive"))
      (node (ref "D357") (pin "9") (pinfunction "NC_9") (pintype "passive"))
      (node (ref "IC353") (pin "17") (pinfunction "RX_AP-_17") (pintype "passive"))
    )
    (net (code "77") (name "/USBF2_XRX_P") (class "Default")
      (node (ref "C375") (pin "2") (pinfunction "2_2") (pintype "passive"))
      (node (ref "D357") (pin "1") (pinfunction "CH1_1") (pintype "passive"))
      (node (ref "D357") (pin "10") (pinfunction "NC_10") (pintype "passive"))
      (node (ref "IC353") (pin "18") (pinfunction "RX_AP+_18") (pintype "passive"))
    )
    (net (code "78") (name "/USBF2_XTX1_N") (class "Default")
      (node (ref "C369") (pin "1") (pinfunction "1_1") (pintype "passive"))
      (node (ref "IC353") (pin "7") (pinfunction "TX_CON_1-_7") (pintype "passive"))
    )
    (net (code "79") (name "/USBF2_XTX1_P") (class "Default")
      (node (ref "C323") (pin "1") (pinfunction "1_1") (pintype "passive"))
      (node (ref "IC353") (pin "6") (pinfunction "TX_CON_1+_6") (pintype "passive"))
    )
    (net (code "80") (name "/USBF2_XTX2_N") (class "Default")
      (node (ref "C373") (pin "1") (pinfunction "1_1") (pintype "passive"))
      (node (ref "IC353") (pin "12") (pinfunction "TX_CON_2+_12") (pintype "passive"))
    )
    (net (code "81") (name "/USBF2_XTX2_P") (class "Default")
      (node (ref "C377") (pin "1") (pinfunction "1_1") (pintype "passive"))
      (node (ref "IC353") (pin "11") (pinfunction "TX_CON_2-_11") (pintype "passive"))
    )
    (net (code "82") (name "/USBF2_XTX_N") (class "Default")
      (node (ref "C321") (pin "2") (pinfunction "2_2") (pintype "passive"))
      (node (ref "D357") (pin "5") (pinfunction "CH4_5") (pintype "passive"))
      (node (ref "D357") (pin "6") (pinfunction "NC_6") (pintype "passive"))
      (node (ref "IC353") (pin "14") (pinfunction "TX_AP-_14") (pintype "passive"))
    )
    (net (code "83") (name "/USBF2_XTX_P") (class "Default")
      (node (ref "C367") (pin "2") (pinfunction "2_2") (pintype "passive"))
      (node (ref "D357") (pin "4") (pinfunction "CH3_4") (pintype "passive"))
      (node (ref "D357") (pin "7") (pinfunction "NC_7") (pintype "passive"))
      (node (ref "IC353") (pin "15") (pinfunction "TX_AP+_15") (pintype "passive"))
    )
    (net (code "84") (name "/USBF3_5V") (class "Default")
      (node (ref "CO304") (pin "24") (pinfunction "B4_24") (pintype "passive"))
      (node (ref "CO304") (pin "29") (pinfunction "B9_29") (pintype "passive"))
      (node (ref "CO304") (pin "4") (pinfunction "A4_4") (pintype "passive"))
      (node (ref "CO304") (pin "9") (pinfunction "A9_9") (pintype "passive"))
    )
    (net (code "85") (name "/USBF3_CC1") (class "Default")
      (node (ref "CO304") (pin "5") (pinfunction "A5_5") (pintype "passive"))
    )
    (net (code "86") (name "/USBF3_CC2") (class "Default")
      (node (ref "CO304") (pin "25") (pinfunction "B5_25") (pintype "passive"))
    )
    (net (code "87") (name "/USBF3_N") (class "Default")
      (node (ref "CO304") (pin "27") (pinfunction "B7_27") (pintype "passive"))
      (node (ref "CO304") (pin "7") (pinfunction "A7_7") (pintype "passive"))
      (node (ref "D356") (pin "1") (pinfunction "D+_1") (pintype "passive"))
    )
    (net (code "88") (name "/USBF3_P") (class "Default")
      (node (ref "CO304") (pin "26") (pinfunction "B6_26") (pintype "passive"))
      (node (ref "CO304") (pin "6") (pinfunction "A6_6") (pintype "passive"))
      (node (ref "D356") (pin "2") (pinfunction "D-_2") (pintype "passive"))
    )
    (net (code "89") (name "/USBF3_RX1_N") (class "Default")
      (node (ref "CO304") (pin "30") (pinfunction "B10_30") (pintype "passive"))
      (node (ref "IC354") (pin "2") (pinfunction "RX_CON_1+_2") (pintype "passive"))
    )
    (net (code "90") (name "/USBF3_RX1_P") (class "Default")
      (node (ref "CO304") (pin "31") (pinfunction "B11_31") (pintype "passive"))
      (node (ref "IC354") (pin "3") (pinfunction "RX_CON_1-_3") (pintype "passive"))
    )
    (net (code "91") (name "/USBF3_RX2_N") (class "Default")
      (node (ref "CO304") (pin "10") (pinfunction "A10_10") (pintype "passive"))
      (node (ref "IC354") (pin "8") (pinfunction "RX_CON_2-_8") (pintype "passive"))
    )
    (net (code "92") (name "/USBF3_RX2_P") (class "Default")
      (node (ref "CO304") (pin "11") (pinfunction "A11_11") (pintype "passive"))
      (node (ref "IC354") (pin "9") (pinfunction "RX_CON_2+_9") (pintype "passive"))
    )
    (net (code "93") (name "/USBF3_RX_N") (class "Default")
      (node (ref "C372") (pin "1") (pinfunction "1_1") (pintype "passive"))
    )
    (net (code "94") (name "/USBF3_RX_P") (class "Default")
      (node (ref "C376") (pin "1") (pinfunction "1_1") (pintype "passive"))
    )
    (net (code "95") (name "/USBF3_SEL") (class "Default")
      (node (ref "IC354") (pin "16") (pinfunction "SEL_16") (pintype "passive"))
    )
    (net (code "96") (name "/USBF3_TX1_N") (class "Default")
      (node (ref "C370") (pin "2") (pinfunction "2_2") (pintype "passive"))
      (node (ref "CO304") (pin "3") (pinfunction "A3_3") (pintype "passive"))
    )
    (net (code "97") (name "/USBF3_TX1_P") (class "Default")
      (node (ref "C324") (pin "2") (pinfunction "2_2") (pintype "passive"))
      (node (ref "CO304") (pin "2") (pinfunction "A2_2") (pintype "passive"))
    )
    (net (code "98") (name "/USBF3_TX2_N") (class "Default")
      (node (ref "C374") (pin "2") (pinfunction "2_2") (pintype "passive"))
      (node (ref "CO304") (pin "23") (pinfunction "B3_23") (pintype "passive"))
    )
    (net (code "99") (name "/USBF3_TX2_P") (class "Default")
      (node (ref "C378") (pin "2") (pinfunction "2_2") (pintype "passive"))
      (node (ref "CO304") (pin "22") (pinfunction "B2_22") (pintype "passive"))
    )
    (net (code "100") (name "/USBF3_TX_N") (class "Default")
      (node (ref "C322") (pin "1") (pinfunction "1_1") (pintype "passive"))
    )
    (net (code "101") (name "/USBF3_TX_P") (class "Default")
      (node (ref "C368") (pin "1") (pinfunction "1_1") (pintype "passive"))
    )
    (net (code "102") (name "/USBF3_XRX_N") (class "Default")
      (node (ref "C372") (pin "2") (pinfunction "2_2") (pintype "passive"))
      (node (ref "D358") (pin "2") (pinfunction "CH2_2") (pintype "passive"))
      (node (ref "D358") (pin "9") (pinfunction "NC_9") (pintype "passive"))
      (node (ref "IC354") (pin "17") (pinfunction "RX_AP-_17") (pintype "passive"))
    )
    (net (code "103") (name "/USBF3_XRX_P") (class "Default")
      (node (ref "C376") (pin "2") (pinfunction "2_2") (pintype "passive"))
      (node (ref "D358") (pin "1") (pinfunction "CH1_1") (pintype "passive"))
      (node (ref "D358") (pin "10") (pinfunction "NC_10") (pintype "passive"))
      (node (ref "IC354") (pin "18") (pinfunction "RX_AP+_18") (pintype "passive"))
    )
    (net (code "104") (name "/USBF3_XTX1_N") (class "Default")
      (node (ref "C370") (pin "1") (pinfunction "1_1") (pintype "passive"))
      (node (ref "IC354") (pin "7") (pinfunction "TX_CON_1-_7") (pintype "passive"))
    )
    (net (code "105") (name "/USBF3_XTX1_P") (class "Default")
      (node (ref "C324") (pin "1") (pinfunction "1_1") (pintype "passive"))
      (node (ref "IC354") (pin "6") (pinfunction "TX_CON_1+_6") (pintype "passive"))
    )
    (net (code "106") (name "/USBF3_XTX2_N") (class "Default")
      (node (ref "C374") (pin "1") (pinfunction "1_1") (pintype "passive"))
      (node (ref "IC354") (pin "12") (pinfunction "TX_CON_2+_12") (pintype "passive"))
    )
    (net (code "107") (name "/USBF3_XTX2_P") (class "Default")
      (node (ref "C378") (pin "1") (pinfunction "1_1") (pintype "passive"))
      (node (ref "IC354") (pin "11") (pinfunction "TX_CON_2-_11") (pintype "passive"))
    )
    (net (code "108") (name "/USBF3_XTX_N") (class "Default")
      (node (ref "C322") (pin "2") (pinfunction "2_2") (pintype "passive"))
      (node (ref "D358") (pin "5") (pinfunction "CH4_5") (pintype "passive"))
      (node (ref "D358") (pin "6") (pinfunction "NC_6") (pintype "passive"))
      (node (ref "IC354") (pin "14") (pinfunction "TX_AP-_14") (pintype "passive"))
    )
    (net (code "109") (name "/USBF3_XTX_P") (class "Default")
      (node (ref "C368") (pin "2") (pinfunction "2_2") (pintype "passive"))
      (node (ref "D358") (pin "4") (pinfunction "CH3_4") (pintype "passive"))
      (node (ref "D358") (pin "7") (pinfunction "NC_7") (pintype "passive"))
      (node (ref "IC354") (pin "15") (pinfunction "TX_AP+_15") (pintype "passive"))
    )
    (net (code "114") (name "GND") (class "Default")
      (node (ref "C318") (pin "2") (pinfunction "2_2") (pintype "passive"))
      (node (ref "C320") (pin "2") (pinfunction "2_2") (pintype "passive"))
      (node (ref "C379") (pin "2") (pinfunction "2_2") (pintype "passive"))
      (node (ref "C380") (pin "2") (pinfunction "2_2") (pintype "passive"))
      (node (ref "CO301") (pin "1") (pinfunction "A1_1") (pintype "passive"))
      (node (ref "CO301") (pin "12") (pinfunction "A12_12") (pintype "passive"))
      (node (ref "CO301") (pin "21") (pinfunction "B1_21") (pintype "passive"))
      (node (ref "CO301") (pin "32") (pinfunction "B12_32") (pintype "passive"))
      (node (ref "CO301") (pin "SH") (pinfunction "SH_SH") (pintype "power_in"))
      (node (ref "CO302") (pin "1") (pinfunction "A1_1") (pintype "passive"))
      (node (ref "CO302") (pin "12") (pinfunction "A12_12") (pintype "passive"))
      (node (ref "CO302") (pin "21") (pinfunction "B1_21") (pintype "passive"))
      (node (ref "CO302") (pin "32") (pinfunction "B12_32") (pintype "passive"))
      (node (ref "CO302") (pin "SH") (pinfunction "SH_SH") (pintype "power_in"))
      (node (ref "CO303") (pin "1") (pinfunction "A1_1") (pintype "passive"))
      (node (ref "CO303") (pin "12") (pinfunction "A12_12") (pintype "passive"))
      (node (ref "CO303") (pin "21") (pinfunction "B1_21") (pintype "passive"))
      (node (ref "CO303") (pin "32") (pinfunction "B12_32") (pintype "passive"))
      (node (ref "CO303") (pin "SH") (pinfunction "SH_SH") (pintype "power_in"))
      (node (ref "CO304") (pin "1") (pinfunction "A1_1") (pintype "passive"))
      (node (ref "CO304") (pin "12") (pinfunction "A12_12") (pintype "passive"))
      (node (ref "CO304") (pin "21") (pinfunction "B1_21") (pintype "passive"))
      (node (ref "CO304") (pin "32") (pinfunction "B12_32") (pintype "passive"))
      (node (ref "CO304") (pin "SH") (pinfunction "SH_SH") (pintype "power_in"))
      (node (ref "D351") (pin "3") (pinfunction "GND_3") (pintype "power_in"))
      (node (ref "D352") (pin "3") (pinfunction "GND_3") (pintype "power_in"))
      (node (ref "D353") (pin "3") (pinfunction "GND_3") (pintype "passive"))
      (node (ref "D353") (pin "8") (pinfunction "GND_8") (pintype "passive"))
      (node (ref "D354") (pin "3") (pinfunction "GND_3") (pintype "passive"))
      (node (ref "D354") (pin "8") (pinfunction "GND_8") (pintype "passive"))
      (node (ref "D355") (pin "3") (pinfunction "GND_3") (pintype "power_in"))
      (node (ref "D356") (pin "3") (pinfunction "GND_3") (pintype "power_in"))
      (node (ref "D357") (pin "3") (pinfunction "GND_3") (pintype "passive"))
      (node (ref "D357") (pin "8") (pinfunction "GND_8") (pintype "passive"))
      (node (ref "D358") (pin "3") (pinfunction "GND_3") (pintype "passive"))
      (node (ref "D358") (pin "8") (pinfunction "GND_8") (pintype "passive"))
      (node (ref "IC351") (pin "19") (pinfunction "GND_19") (pintype "passive"))
      (node (ref "IC352") (pin "19") (pinfunction "GND_19") (pintype "passive"))
      (node (ref "IC353") (pin "19") (pinfunction "GND_19") (pintype "passive"))
      (node (ref "IC354") (pin "19") (pinfunction "GND_19") (pintype "passive"))
    )
    (net (code "116") (name "unconnected-(CO301-A8-Pad8)") (class "Default")
      (node (ref "CO301") (pin "8") (pinfunction "A8_8") (pintype "passive"))
    )
    (net (code "117") (name "unconnected-(CO301-B8-Pad28)") (class "Default")
      (node (ref "CO301") (pin "28") (pinfunction "B8_28") (pintype "passive"))
    )
    (net (code "118") (name "unconnected-(CO302-A8-Pad8)") (class "Default")
      (node (ref "CO302") (pin "8") (pinfunction "A8_8") (pintype "passive"))
    )
    (net (code "119") (name "unconnected-(CO302-B8-Pad28)") (class "Default")
      (node (ref "CO302") (pin "28") (pinfunction "B8_28") (pintype "passive"))
    )
    (net (code "120") (name "unconnected-(CO303-A8-Pad8)") (class "Default")
      (node (ref "CO303") (pin "8") (pinfunction "A8_8") (pintype "passive"))
    )
    (net (code "121") (name "unconnected-(CO303-B8-Pad28)") (class "Default")
      (node (ref "CO303") (pin "28") (pinfunction "B8_28") (pintype "passive"))
    )
    (net (code "122") (name "unconnected-(CO304-A8-Pad8)") (class "Default")
      (node (ref "CO304") (pin "8") (pinfunction "A8_8") (pintype "passive"))
    )
    (net (code "123") (name "unconnected-(CO304-B8-Pad28)") (class "Default")
      (node (ref "CO304") (pin "28") (pinfunction "B8_28") (pintype "passive"))
    )
    (net (code "124") (name "unconnected-(IC351-CNFG_A1-Pad1)") (class "Default")
      (node (ref "IC351") (pin "1") (pinfunction "CNFG_A1_1") (pintype "passive"))
    )
    (net (code "125") (name "unconnected-(IC351-CNFG_A2-Pad13)") (class "Default")
      (node (ref "IC351") (pin "13") (pinfunction "CNFG_A2_13") (pintype "passive"))
    )
    (net (code "126") (name "unconnected-(IC351-CNFG_B1-Pad4)") (class "Default")
      (node (ref "IC351") (pin "4") (pinfunction "CNFG_B1_4") (pintype "passive"))
    )
    (net (code "127") (name "unconnected-(IC351-CNFG_B2-Pad10)") (class "Default")
      (node (ref "IC351") (pin "10") (pinfunction "CNFG_B2_10") (pintype "passive"))
    )
    (net (code "128") (name "unconnected-(IC352-CNFG_A1-Pad1)") (class "Default")
      (node (ref "IC352") (pin "1") (pinfunction "CNFG_A1_1") (pintype "passive"))
    )
    (net (code "129") (name "unconnected-(IC352-CNFG_A2-Pad13)") (class "Default")
      (node (ref "IC352") (pin "13") (pinfunction "CNFG_A2_13") (pintype "passive"))
    )
    (net (code "130") (name "unconnected-(IC352-CNFG_B1-Pad4)") (class "Default")
      (node (ref "IC352") (pin "4") (pinfunction "CNFG_B1_4") (pintype "passive"))
    )
    (net (code "131") (name "unconnected-(IC352-CNFG_B2-Pad10)") (class "Default")
      (node (ref "IC352") (pin "10") (pinfunction "CNFG_B2_10") (pintype "passive"))
    )
    (net (code "132") (name "unconnected-(IC353-CNFG_A1-Pad1)") (class "Default")
      (node (ref "IC353") (pin "1") (pinfunction "CNFG_A1_1") (pintype "passive"))
    )
    (net (code "133") (name "unconnected-(IC353-CNFG_A2-Pad13)") (class "Default")
      (node (ref "IC353") (pin "13") (pinfunction "CNFG_A2_13") (pintype "passive"))
    )
    (net (code "134") (name "unconnected-(IC353-CNFG_B1-Pad4)") (class "Default")
      (node (ref "IC353") (pin "4") (pinfunction "CNFG_B1_4") (pintype "passive"))
    )
    (net (code "135") (name "unconnected-(IC353-CNFG_B2-Pad10)") (class "Default")
      (node (ref "IC353") (pin "10") (pinfunction "CNFG_B2_10") (pintype "passive"))
    )
    (net (code "136") (name "unconnected-(IC354-CNFG_A1-Pad1)") (class "Default")
      (node (ref "IC354") (pin "1") (pinfunction "CNFG_A1_1") (pintype "passive"))
    )
    (net (code "137") (name "unconnected-(IC354-CNFG_A2-Pad13)") (class "Default")
      (node (ref "IC354") (pin "13") (pinfunction "CNFG_A2_13") (pintype "passive"))
    )
    (net (code "138") (name "unconnected-(IC354-CNFG_B1-Pad4)") (class "Default")
      (node (ref "IC354") (pin "4") (pinfunction "CNFG_B1_4") (pintype "passive"))
    )
    (net (code "139") (name "unconnected-(IC354-CNFG_B2-Pad10)") (class "Default")
      (node (ref "IC354") (pin "10") (pinfunction "CNFG_B2_10") (pintype "passive"))
    )
  )
)
